# CW308T_M2351_Main.net
KiCad netlist of a schematic drawn in Altium Designer
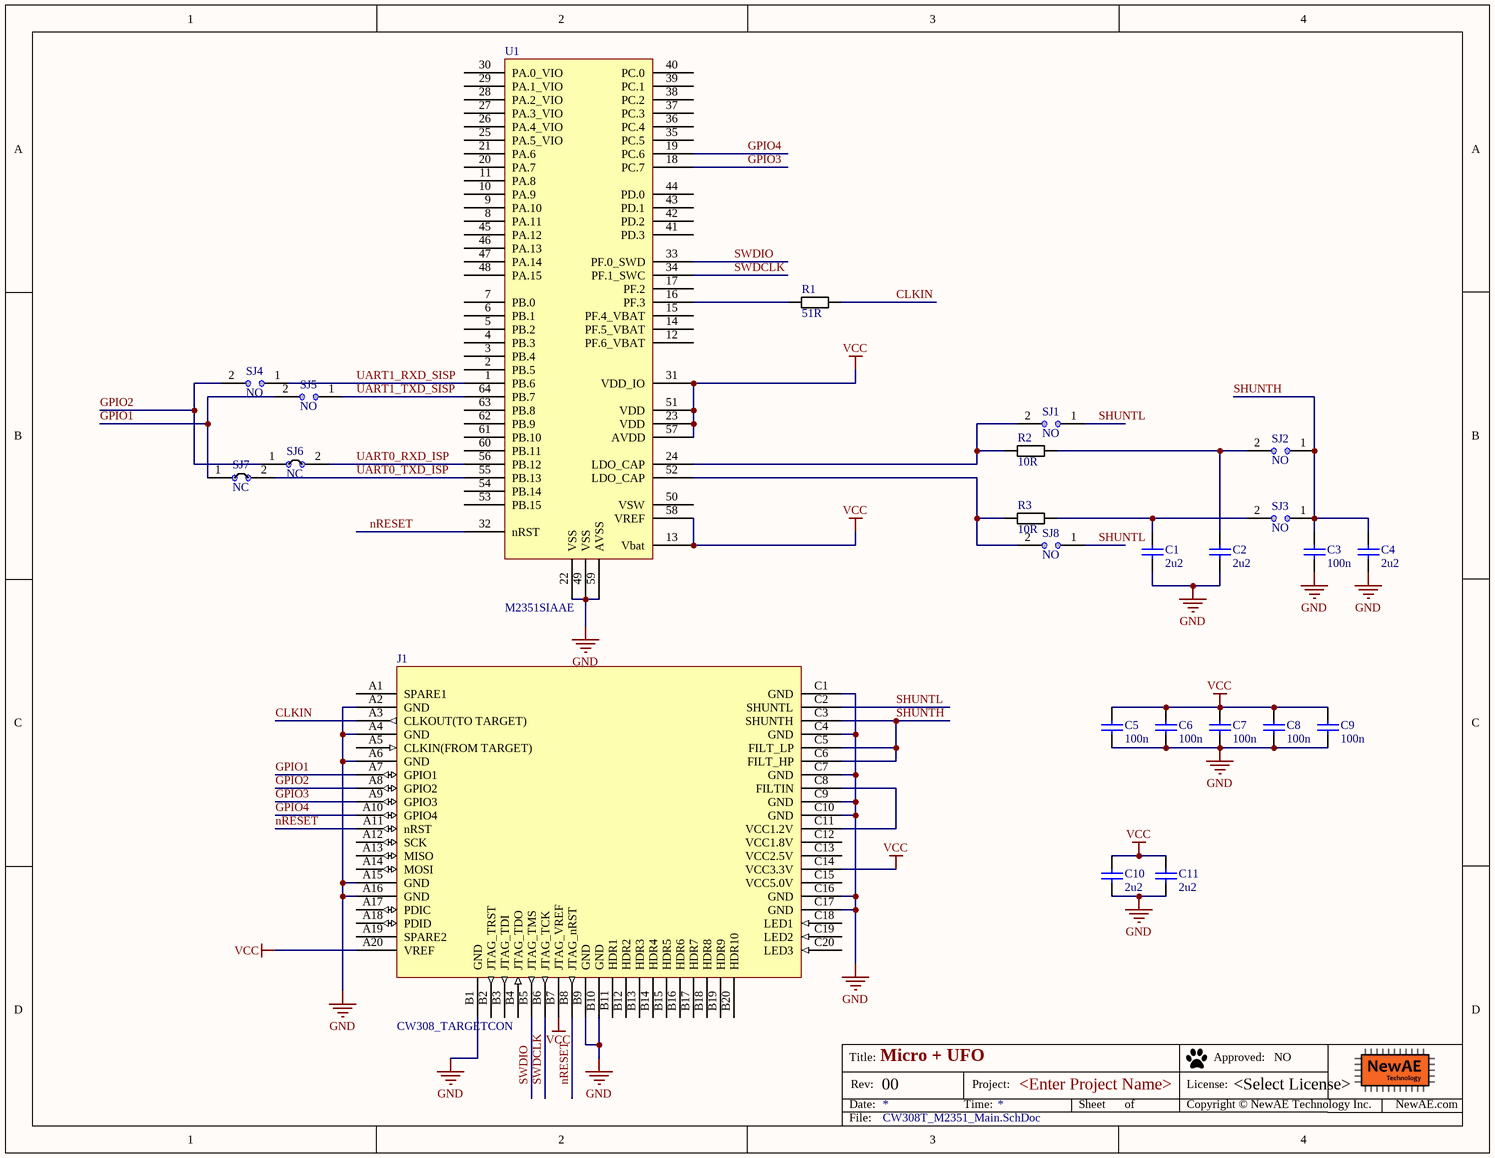
[diagram p0: CW308T_M2351_Main.SchDoc]

(export (version "E")
  (design (tool "Eeschema 10.0.6"))
  (components
    (comp (ref "C1")
      (value "2u2")
      (footprint "CAPC0603_M")
      (description "2u2, 0603")
      (fields (field (name "PART NUMBER") "CCHIP-2u2-0603"))
      (libsource (lib "NewAE_AltiumLib") (part "CAP"))
    )
    (comp (ref "C2")
      (value "2u2")
      (footprint "CAPC0603_M")
      (description "2u2, 0603")
      (fields (field (name "PART NUMBER") "CCHIP-2u2-0603"))
      (libsource (lib "NewAE_AltiumLib") (part "CAP"))
    )
    (comp (ref "C3")
      (value "100n")
      (footprint "CAPC0603_M")
      (description "100n, 0603")
      (fields (field (name "PART NUMBER") "CCHIP-100n-0603"))
      (libsource (lib "NewAE_AltiumLib") (part "CAP"))
    )
    (comp (ref "C4")
      (value "2u2")
      (footprint "CAPC0603_M")
      (description "2u2, 0603")
      (fields (field (name "PART NUMBER") "CCHIP-2u2-0603"))
      (libsource (lib "NewAE_AltiumLib") (part "CAP"))
    )
    (comp (ref "C5")
      (value "100n")
      (footprint "CAPC0603_M")
      (description "100n, 0603")
      (fields (field (name "PART NUMBER") "CCHIP-100n-0603"))
      (libsource (lib "NewAE_AltiumLib") (part "CAP"))
    )
    (comp (ref "C6")
      (value "100n")
      (footprint "CAPC0603_M")
      (description "100n, 0603")
      (fields (field (name "PART NUMBER") "CCHIP-100n-0603"))
      (libsource (lib "NewAE_AltiumLib") (part "CAP"))
    )
    (comp (ref "C7")
      (value "100n")
      (footprint "CAPC0603_M")
      (description "100n, 0603")
      (fields (field (name "PART NUMBER") "CCHIP-100n-0603"))
      (libsource (lib "NewAE_AltiumLib") (part "CAP"))
    )
    (comp (ref "C8")
      (value "100n")
      (footprint "CAPC0603_M")
      (description "100n, 0603")
      (fields (field (name "PART NUMBER") "CCHIP-100n-0603"))
      (libsource (lib "NewAE_AltiumLib") (part "CAP"))
    )
    (comp (ref "C9")
      (value "100n")
      (footprint "CAPC0603_M")
      (description "100n, 0603")
      (fields (field (name "PART NUMBER") "CCHIP-100n-0603"))
      (libsource (lib "NewAE_AltiumLib") (part "CAP"))
    )
    (comp (ref "C10")
      (value "2u2")
      (footprint "CAPC0603_M")
      (description "2u2, 0603")
      (fields (field (name "PART NUMBER") "CCHIP-2u2-0603"))
      (libsource (lib "NewAE_AltiumLib") (part "CAP"))
    )
    (comp (ref "C11")
      (value "2u2")
      (footprint "CAPC0603_M")
      (description "2u2, 0603")
      (fields (field (name "PART NUMBER") "CCHIP-2u2-0603"))
      (libsource (lib "NewAE_AltiumLib") (part "CAP"))
    )
    (comp (ref "J1")
      (value "CW308_TARGETCON")
      (footprint "CW308_TBOARD_CONN")
      (description "CW308 \"Standard\" Target Board Connector")
      (fields (field (name "PART NUMBER") "CW308_TBOARD"))
      (libsource (lib "NewAE_AltiumLib") (part "CW308_TBOARD"))
    )
    (comp (ref "R1")
      (value "51R")
      (footprint "RESC1608X55N")
      (description "51R res, 0603, 1%, 1/10W")
      (fields (field (name "PART NUMBER") "RCHIP-51R-0603") (field (name "TOLERANCE") "1%"))
      (libsource (lib "NewAE_AltiumLib") (part "RES-EU"))
    )
    (comp (ref "R2")
      (value "10R")
      (footprint "RESC1608X55N")
      (description "10R res, 0603, 1%, 1/10W")
      (fields (field (name "PART NUMBER") "RCHIP-10R-0603") (field (name "TOLERANCE") "1%"))
      (libsource (lib "NewAE_AltiumLib") (part "RES-EU"))
    )
    (comp (ref "R3")
      (value "10R")
      (footprint "RESC1608X55N")
      (description "10R res, 0603, 1%, 1/10W")
      (fields (field (name "PART NUMBER") "RCHIP-10R-0603") (field (name "TOLERANCE") "1%"))
      (libsource (lib "NewAE_AltiumLib") (part "RES-EU"))
    )
    (comp (ref "SJ1")
      (value "NO")
      (footprint "SJ_2S_NO")
      (description "Solder Jumper, NO")
      (fields (field (name "PART NUMBER") "SJ_2S_NO"))
      (libsource (lib "NewAE_AltiumLib") (part "SJ_2S_NO"))
    )
    (comp (ref "SJ2")
      (value "NO")
      (footprint "SJ_2S_NO")
      (description "Solder Jumper, NO")
      (fields (field (name "PART NUMBER") "SJ_2S_NO"))
      (libsource (lib "NewAE_AltiumLib") (part "SJ_2S_NO"))
    )
    (comp (ref "SJ3")
      (value "NO")
      (footprint "SJ_2S_NO")
      (description "Solder Jumper, NO")
      (fields (field (name "PART NUMBER") "SJ_2S_NO"))
      (libsource (lib "NewAE_AltiumLib") (part "SJ_2S_NO"))
    )
    (comp (ref "SJ4")
      (value "NO")
      (footprint "SJ_2S_NO")
      (description "Solder Jumper, NO")
      (fields (field (name "PART NUMBER") "SJ_2S_NO"))
      (libsource (lib "NewAE_AltiumLib") (part "SJ_2S_NO"))
    )
    (comp (ref "SJ5")
      (value "NO")
      (footprint "SJ_2S_NO")
      (description "Solder Jumper, NO")
      (fields (field (name "PART NUMBER") "SJ_2S_NO"))
      (libsource (lib "NewAE_AltiumLib") (part "SJ_2S_NO"))
    )
    (comp (ref "SJ6")
      (value "NC")
      (footprint "SJ_2S_NC")
      (description "Solder Jumper, NC")
      (fields (field (name "PART NUMBER") "SJ_2S"))
      (libsource (lib "NewAE_AltiumLib") (part "SJ_2S"))
    )
    (comp (ref "SJ7")
      (value "NC")
      (footprint "SJ_2S_NC")
      (description "Solder Jumper, NC")
      (fields (field (name "PART NUMBER") "SJ_2S"))
      (libsource (lib "NewAE_AltiumLib") (part "SJ_2S"))
    )
    (comp (ref "SJ8")
      (value "NO")
      (footprint "SJ_2S_NO")
      (description "Solder Jumper, NO")
      (fields (field (name "PART NUMBER") "SJ_2S_NO"))
      (libsource (lib "NewAE_AltiumLib") (part "SJ_2S_NO"))
    )
    (comp (ref "U1")
      (value "M2351SIAAE")
      (footprint "TQFP50P1200X1200X120-64N")
      (description "Cortex M23 Device, QFP64")
      (libsource (lib "NewAE_AltiumLib") (part "M2351SIAAE"))
    )
  )
  (nets
    (net (code "1") (name "/CLKIN") (class "Default")
      (node (ref "J1") (pin "A3") (pinfunction "CLKOUT(TO_TARGET)_A3") (pintype "output"))
      (node (ref "R1") (pin "2") (pinfunction "2_2") (pintype "passive"))
    )
    (net (code "2") (name "/GPIO1") (class "Default")
      (node (ref "J1") (pin "A7") (pinfunction "GPIO1_A7") (pintype "bidirectional"))
      (node (ref "SJ5") (pin "2") (pinfunction "2_2") (pintype "passive"))
      (node (ref "SJ7") (pin "1") (pinfunction "1_1") (pintype "passive"))
    )
    (net (code "3") (name "/GPIO2") (class "Default")
      (node (ref "J1") (pin "A8") (pinfunction "GPIO2_A8") (pintype "bidirectional"))
      (node (ref "SJ4") (pin "2") (pinfunction "2_2") (pintype "passive"))
      (node (ref "SJ6") (pin "1") (pinfunction "1_1") (pintype "passive"))
    )
    (net (code "4") (name "/GPIO3") (class "Default")
      (node (ref "J1") (pin "A9") (pinfunction "GPIO3_A9") (pintype "bidirectional"))
      (node (ref "U1") (pin "18") (pinfunction "PC.7_18") (pintype "passive"))
    )
    (net (code "5") (name "/GPIO4") (class "Default")
      (node (ref "J1") (pin "A10") (pinfunction "GPIO4_A10") (pintype "bidirectional"))
      (node (ref "U1") (pin "19") (pinfunction "PC.6_19") (pintype "passive"))
    )
    (net (code "6") (name "/SHUNTH") (class "Default")
      (node (ref "C3") (pin "1") (pinfunction "1_1") (pintype "passive"))
      (node (ref "C4") (pin "1") (pinfunction "1_1") (pintype "passive"))
      (node (ref "J1") (pin "C3") (pinfunction "SHUNTH_C3") (pintype "passive"))
      (node (ref "J1") (pin "C5") (pinfunction "FILT_LP_C5") (pintype "passive"))
      (node (ref "J1") (pin "C6") (pinfunction "FILT_HP_C6") (pintype "passive"))
      (node (ref "SJ2") (pin "1") (pinfunction "1_1") (pintype "passive"))
      (node (ref "SJ3") (pin "1") (pinfunction "1_1") (pintype "passive"))
    )
    (net (code "7") (name "/SHUNTL") (class "Default")
      (node (ref "J1") (pin "C2") (pinfunction "SHUNTL_C2") (pintype "passive"))
      (node (ref "SJ1") (pin "1") (pinfunction "1_1") (pintype "passive"))
      (node (ref "SJ8") (pin "1") (pinfunction "1_1") (pintype "passive"))
    )
    (net (code "8") (name "/SWDCLK") (class "Default")
      (node (ref "J1") (pin "B6") (pinfunction "JTAG_TCK_B6") (pintype "output"))
      (node (ref "U1") (pin "34") (pinfunction "PF.1_SWC_34") (pintype "passive"))
    )
    (net (code "9") (name "/SWDIO") (class "Default")
      (node (ref "J1") (pin "B5") (pinfunction "JTAG_TMS_B5") (pintype "output"))
      (node (ref "U1") (pin "33") (pinfunction "PF.0_SWD_33") (pintype "passive"))
    )
    (net (code "10") (name "/UART0_RXD_ISP") (class "Default")
      (node (ref "SJ6") (pin "2") (pinfunction "2_2") (pintype "passive"))
      (node (ref "U1") (pin "56") (pinfunction "PB.12_56") (pintype "passive"))
    )
    (net (code "11") (name "/UART0_TXD_ISP") (class "Default")
      (node (ref "SJ7") (pin "2") (pinfunction "2_2") (pintype "passive"))
      (node (ref "U1") (pin "55") (pinfunction "PB.13_55") (pintype "passive"))
    )
    (net (code "12") (name "/UART1_RXD_SISP") (class "Default")
      (node (ref "SJ4") (pin "1") (pinfunction "1_1") (pintype "passive"))
      (node (ref "U1") (pin "1") (pinfunction "PB.6_1") (pintype "passive"))
    )
    (net (code "13") (name "/UART1_TXD_SISP") (class "Default")
      (node (ref "SJ5") (pin "1") (pinfunction "1_1") (pintype "passive"))
      (node (ref "U1") (pin "64") (pinfunction "PB.7_64") (pintype "passive"))
    )
    (net (code "14") (name "/nRESET") (class "Default")
      (node (ref "J1") (pin "A11") (pinfunction "nRST_A11") (pintype "bidirectional"))
      (node (ref "J1") (pin "B8") (pinfunction "JTAG_nRST_B8") (pintype "output"))
      (node (ref "U1") (pin "32") (pinfunction "nRST_32") (pintype "passive"))
    )
    (net (code "15") (name "GND") (class "Default")
      (node (ref "C1") (pin "2") (pinfunction "2_2") (pintype "passive"))
      (node (ref "C10") (pin "2") (pinfunction "2_2") (pintype "passive"))
      (node (ref "C11") (pin "2") (pinfunction "2_2") (pintype "passive"))
      (node (ref "C2") (pin "2") (pinfunction "2_2") (pintype "passive"))
      (node (ref "C3") (pin "2") (pinfunction "2_2") (pintype "passive"))
      (node (ref "C4") (pin "2") (pinfunction "2_2") (pintype "passive"))
      (node (ref "C5") (pin "2") (pinfunction "2_2") (pintype "passive"))
      (node (ref "C6") (pin "2") (pinfunction "2_2") (pintype "passive"))
      (node (ref "C7") (pin "2") (pinfunction "2_2") (pintype "passive"))
      (node (ref "C8") (pin "2") (pinfunction "2_2") (pintype "passive"))
      (node (ref "C9") (pin "2") (pinfunction "2_2") (pintype "passive"))
      (node (ref "J1") (pin "A15") (pinfunction "GND_A15") (pintype "passive"))
      (node (ref "J1") (pin "A16") (pinfunction "GND_A16") (pintype "passive"))
      (node (ref "J1") (pin "A2") (pinfunction "GND_A2") (pintype "passive"))
      (node (ref "J1") (pin "A4") (pinfunction "GND_A4") (pintype "passive"))
      (node (ref "J1") (pin "A6") (pinfunction "GND_A6") (pintype "power_in"))
      (node (ref "J1") (pin "B1") (pinfunction "GND_B1") (pintype "passive"))
      (node (ref "J1") (pin "B10") (pinfunction "GND_B10") (pintype "passive"))
      (node (ref "J1") (pin "B9") (pinfunction "GND_B9") (pintype "passive"))
      (node (ref "J1") (pin "C1") (pinfunction "GND_C1") (pintype "power_in"))
      (node (ref "J1") (pin "C10") (pinfunction "GND_C10") (pintype "power_in"))
      (node (ref "J1") (pin "C16") (pinfunction "GND_C16") (pintype "power_in"))
      (node (ref "J1") (pin "C17") (pinfunction "GND_C17") (pintype "power_in"))
      (node (ref "J1") (pin "C4") (pinfunction "GND_C4") (pintype "power_in"))
      (node (ref "J1") (pin "C7") (pinfunction "GND_C7") (pintype "power_in"))
      (node (ref "J1") (pin "C9") (pinfunction "GND_C9") (pintype "power_in"))
      (node (ref "U1") (pin "22") (pinfunction "VSS_22") (pintype "passive"))
      (node (ref "U1") (pin "49") (pinfunction "VSS_49") (pintype "passive"))
      (node (ref "U1") (pin "59") (pinfunction "AVSS_59") (pintype "passive"))
    )
    (net (code "16") (name "Net-(C1-Pad1)") (class "Default")
      (node (ref "C1") (pin "1") (pinfunction "1_1") (pintype "passive"))
      (node (ref "R3") (pin "2") (pinfunction "2_2") (pintype "passive"))
      (node (ref "SJ3") (pin "2") (pinfunction "2_2") (pintype "passive"))
    )
    (net (code "17") (name "Net-(C2-Pad1)") (class "Default")
      (node (ref "C2") (pin "1") (pinfunction "1_1") (pintype "passive"))
      (node (ref "R2") (pin "2") (pinfunction "2_2") (pintype "passive"))
      (node (ref "SJ2") (pin "2") (pinfunction "2_2") (pintype "passive"))
    )
    (net (code "18") (name "Net-(J1-FILTIN)") (class "Default")
      (node (ref "J1") (pin "C11") (pinfunction "VCC1.2V_C11") (pintype "power_in"))
      (node (ref "J1") (pin "C8") (pinfunction "FILTIN_C8") (pintype "passive"))
    )
    (net (code "19") (name "Net-(R2-Pad1)") (class "Default")
      (node (ref "R2") (pin "1") (pinfunction "1_1") (pintype "passive"))
      (node (ref "SJ1") (pin "2") (pinfunction "2_2") (pintype "passive"))
      (node (ref "U1") (pin "24") (pinfunction "LDO_CAP_24") (pintype "passive"))
    )
    (net (code "20") (name "Net-(R3-Pad1)") (class "Default")
      (node (ref "R3") (pin "1") (pinfunction "1_1") (pintype "passive"))
      (node (ref "SJ8") (pin "2") (pinfunction "2_2") (pintype "passive"))
      (node (ref "U1") (pin "52") (pinfunction "LDO_CAP_52") (pintype "passive"))
    )
    (net (code "21") (name "Net-(U1-PF.3)") (class "Default")
      (node (ref "R1") (pin "1") (pinfunction "1_1") (pintype "passive"))
      (node (ref "U1") (pin "16") (pinfunction "PF.3_16") (pintype "passive"))
    )
    (net (code "22") (name "VCC") (class "Default")
      (node (ref "C10") (pin "1") (pinfunction "1_1") (pintype "passive"))
      (node (ref "C11") (pin "1") (pinfunction "1_1") (pintype "passive"))
      (node (ref "C5") (pin "1") (pinfunction "1_1") (pintype "passive"))
      (node (ref "C6") (pin "1") (pinfunction "1_1") (pintype "passive"))
      (node (ref "C7") (pin "1") (pinfunction "1_1") (pintype "passive"))
      (node (ref "C8") (pin "1") (pinfunction "1_1") (pintype "passive"))
      (node (ref "C9") (pin "1") (pinfunction "1_1") (pintype "passive"))
      (node (ref "J1") (pin "A20") (pinfunction "VREF_A20") (pintype "tri_state"))
      (node (ref "J1") (pin "B7") (pinfunction "JTAG_VREF_B7") (pintype "tri_state"))
      (node (ref "J1") (pin "C14") (pinfunction "VCC3.3V_C14") (pintype "power_in"))
      (node (ref "U1") (pin "13") (pinfunction "Vbat_13") (pintype "passive"))
      (node (ref "U1") (pin "23") (pinfunction "VDD_23") (pintype "passive"))
      (node (ref "U1") (pin "31") (pinfunction "VDD_IO_31") (pintype "passive"))
      (node (ref "U1") (pin "51") (pinfunction "VDD_51") (pintype "passive"))
      (node (ref "U1") (pin "57") (pinfunction "AVDD_57") (pintype "passive"))
      (node (ref "U1") (pin "58") (pinfunction "VREF_58") (pintype "passive"))
    )
    (net (code "23") (name "unconnected-(J1-CLKIN(FROM_TARGET)-PadA5)") (class "Default")
      (node (ref "J1") (pin "A5") (pinfunction "CLKIN(FROM_TARGET)_A5") (pintype "input"))
    )
    (net (code "24") (name "unconnected-(J1-HDR1-PadB11)") (class "Default")
      (node (ref "J1") (pin "B11") (pinfunction "HDR1_B11") (pintype "passive"))
    )
    (net (code "25") (name "unconnected-(J1-HDR2-PadB12)") (class "Default")
      (node (ref "J1") (pin "B12") (pinfunction "HDR2_B12") (pintype "passive"))
    )
    (net (code "26") (name "unconnected-(J1-HDR3-PadB13)") (class "Default")
      (node (ref "J1") (pin "B13") (pinfunction "HDR3_B13") (pintype "passive"))
    )
    (net (code "27") (name "unconnected-(J1-HDR4-PadB14)") (class "Default")
      (node (ref "J1") (pin "B14") (pinfunction "HDR4_B14") (pintype "passive"))
    )
    (net (code "28") (name "unconnected-(J1-HDR5-PadB15)") (class "Default")
      (node (ref "J1") (pin "B15") (pinfunction "HDR5_B15") (pintype "passive"))
    )
    (net (code "29") (name "unconnected-(J1-HDR6-PadB16)") (class "Default")
      (node (ref "J1") (pin "B16") (pinfunction "HDR6_B16") (pintype "passive"))
    )
    (net (code "30") (name "unconnected-(J1-HDR7-PadB17)") (class "Default")
      (node (ref "J1") (pin "B17") (pinfunction "HDR7_B17") (pintype "passive"))
    )
    (net (code "31") (name "unconnected-(J1-HDR8-PadB18)") (class "Default")
      (node (ref "J1") (pin "B18") (pinfunction "HDR8_B18") (pintype "passive"))
    )
    (net (code "32") (name "unconnected-(J1-HDR9-PadB19)") (class "Default")
      (node (ref "J1") (pin "B19") (pinfunction "HDR9_B19") (pintype "passive"))
    )
    (net (code "33") (name "unconnected-(J1-HDR10-PadB20)") (class "Default")
      (node (ref "J1") (pin "B20") (pinfunction "HDR10_B20") (pintype "passive"))
    )
    (net (code "34") (name "unconnected-(J1-JTAG_TDI-PadB3)") (class "Default")
      (node (ref "J1") (pin "B3") (pinfunction "JTAG_TDI_B3") (pintype "output"))
    )
    (net (code "35") (name "unconnected-(J1-JTAG_TDO-PadB4)") (class "Default")
      (node (ref "J1") (pin "B4") (pinfunction "JTAG_TDO_B4") (pintype "input"))
    )
    (net (code "36") (name "unconnected-(J1-JTAG_TRST-PadB2)") (class "Default")
      (node (ref "J1") (pin "B2") (pinfunction "JTAG_TRST_B2") (pintype "output"))
    )
    (net (code "37") (name "unconnected-(J1-LED1-PadC18)") (class "Default")
      (node (ref "J1") (pin "C18") (pinfunction "LED1_C18") (pintype "input"))
    )
    (net (code "38") (name "unconnected-(J1-LED2-PadC19)") (class "Default")
      (node (ref "J1") (pin "C19") (pinfunction "LED2_C19") (pintype "input"))
    )
    (net (code "39") (name "unconnected-(J1-LED3-PadC20)") (class "Default")
      (node (ref "J1") (pin "C20") (pinfunction "LED3_C20") (pintype "input"))
    )
    (net (code "40") (name "unconnected-(J1-MISO-PadA13)") (class "Default")
      (node (ref "J1") (pin "A13") (pinfunction "MISO_A13") (pintype "bidirectional"))
    )
    (net (code "41") (name "unconnected-(J1-MOSI-PadA14)") (class "Default")
      (node (ref "J1") (pin "A14") (pinfunction "MOSI_A14") (pintype "bidirectional"))
    )
    (net (code "42") (name "unconnected-(J1-PDIC-PadA17)") (class "Default")
      (node (ref "J1") (pin "A17") (pinfunction "PDIC_A17") (pintype "bidirectional"))
    )
    (net (code "43") (name "unconnected-(J1-PDID-PadA18)") (class "Default")
      (node (ref "J1") (pin "A18") (pinfunction "PDID_A18") (pintype "bidirectional"))
    )
    (net (code "44") (name "unconnected-(J1-SCK-PadA12)") (class "Default")
      (node (ref "J1") (pin "A12") (pinfunction "SCK_A12") (pintype "bidirectional"))
    )
    (net (code "45") (name "unconnected-(J1-SPARE1-PadA1)") (class "Default")
      (node (ref "J1") (pin "A1") (pinfunction "SPARE1_A1") (pintype "passive"))
    )
    (net (code "46") (name "unconnected-(J1-SPARE2-PadA19)") (class "Default")
      (node (ref "J1") (pin "A19") (pinfunction "SPARE2_A19") (pintype "passive"))
    )
    (net (code "47") (name "unconnected-(J1-VCC1.8V-PadC12)") (class "Default")
      (node (ref "J1") (pin "C12") (pinfunction "VCC1.8V_C12") (pintype "power_in"))
    )
    (net (code "48") (name "unconnected-(J1-VCC2.5V-PadC13)") (class "Default")
      (node (ref "J1") (pin "C13") (pinfunction "VCC2.5V_C13") (pintype "power_in"))
    )
    (net (code "49") (name "unconnected-(J1-VCC5.0V-PadC15)") (class "Default")
      (node (ref "J1") (pin "C15") (pinfunction "VCC5.0V_C15") (pintype "power_in"))
    )
    (net (code "50") (name "unconnected-(U1-PA.0_VIO-Pad30)") (class "Default")
      (node (ref "U1") (pin "30") (pinfunction "PA.0_VIO_30") (pintype "passive"))
    )
    (net (code "51") (name "unconnected-(U1-PA.1_VIO-Pad29)") (class "Default")
      (node (ref "U1") (pin "29") (pinfunction "PA.1_VIO_29") (pintype "passive"))
    )
    (net (code "52") (name "unconnected-(U1-PA.2_VIO-Pad28)") (class "Default")
      (node (ref "U1") (pin "28") (pinfunction "PA.2_VIO_28") (pintype "passive"))
    )
    (net (code "53") (name "unconnected-(U1-PA.3_VIO-Pad27)") (class "Default")
      (node (ref "U1") (pin "27") (pinfunction "PA.3_VIO_27") (pintype "passive"))
    )
    (net (code "54") (name "unconnected-(U1-PA.4_VIO-Pad26)") (class "Default")
      (node (ref "U1") (pin "26") (pinfunction "PA.4_VIO_26") (pintype "passive"))
    )
    (net (code "55") (name "unconnected-(U1-PA.5_VIO-Pad25)") (class "Default")
      (node (ref "U1") (pin "25") (pinfunction "PA.5_VIO_25") (pintype "passive"))
    )
    (net (code "56") (name "unconnected-(U1-PA.6-Pad21)") (class "Default")
      (node (ref "U1") (pin "21") (pinfunction "PA.6_21") (pintype "passive"))
    )
    (net (code "57") (name "unconnected-(U1-PA.7-Pad20)") (class "Default")
      (node (ref "U1") (pin "20") (pinfunction "PA.7_20") (pintype "passive"))
    )
    (net (code "58") (name "unconnected-(U1-PA.8-Pad11)") (class "Default")
      (node (ref "U1") (pin "11") (pinfunction "PA.8_11") (pintype "passive"))
    )
    (net (code "59") (name "unconnected-(U1-PA.9-Pad10)") (class "Default")
      (node (ref "U1") (pin "10") (pinfunction "PA.9_10") (pintype "passive"))
    )
    (net (code "60") (name "unconnected-(U1-PA.10-Pad9)") (class "Default")
      (node (ref "U1") (pin "9") (pinfunction "PA.10_9") (pintype "passive"))
    )
    (net (code "61") (name "unconnected-(U1-PA.11-Pad8)") (class "Default")
      (node (ref "U1") (pin "8") (pinfunction "PA.11_8") (pintype "passive"))
    )
    (net (code "62") (name "unconnected-(U1-PA.12-Pad45)") (class "Default")
      (node (ref "U1") (pin "45") (pinfunction "PA.12_45") (pintype "passive"))
    )
    (net (code "63") (name "unconnected-(U1-PA.13-Pad46)") (class "Default")
      (node (ref "U1") (pin "46") (pinfunction "PA.13_46") (pintype "passive"))
    )
    (net (code "64") (name "unconnected-(U1-PA.14-Pad47)") (class "Default")
      (node (ref "U1") (pin "47") (pinfunction "PA.14_47") (pintype "passive"))
    )
    (net (code "65") (name "unconnected-(U1-PA.15-Pad48)") (class "Default")
      (node (ref "U1") (pin "48") (pinfunction "PA.15_48") (pintype "passive"))
    )
    (net (code "66") (name "unconnected-(U1-PB.0-Pad7)") (class "Default")
      (node (ref "U1") (pin "7") (pinfunction "PB.0_7") (pintype "passive"))
    )
    (net (code "67") (name "unconnected-(U1-PB.1-Pad6)") (class "Default")
      (node (ref "U1") (pin "6") (pinfunction "PB.1_6") (pintype "passive"))
    )
    (net (code "68") (name "unconnected-(U1-PB.2-Pad5)") (class "Default")
      (node (ref "U1") (pin "5") (pinfunction "PB.2_5") (pintype "passive"))
    )
    (net (code "69") (name "unconnected-(U1-PB.3-Pad4)") (class "Default")
      (node (ref "U1") (pin "4") (pinfunction "PB.3_4") (pintype "passive"))
    )
    (net (code "70") (name "unconnected-(U1-PB.4-Pad3)") (class "Default")
      (node (ref "U1") (pin "3") (pinfunction "PB.4_3") (pintype "passive"))
    )
    (net (code "71") (name "unconnected-(U1-PB.5-Pad2)") (class "Default")
      (node (ref "U1") (pin "2") (pinfunction "PB.5_2") (pintype "passive"))
    )
    (net (code "72") (name "unconnected-(U1-PB.8-Pad63)") (class "Default")
      (node (ref "U1") (pin "63") (pinfunction "PB.8_63") (pintype "passive"))
    )
    (net (code "73") (name "unconnected-(U1-PB.9-Pad62)") (class "Default")
      (node (ref "U1") (pin "62") (pinfunction "PB.9_62") (pintype "passive"))
    )
    (net (code "74") (name "unconnected-(U1-PB.10-Pad61)") (class "Default")
      (node (ref "U1") (pin "61") (pinfunction "PB.10_61") (pintype "passive"))
    )
    (net (code "75") (name "unconnected-(U1-PB.11-Pad60)") (class "Default")
      (node (ref "U1") (pin "60") (pinfunction "PB.11_60") (pintype "passive"))
    )
    (net (code "76") (name "unconnected-(U1-PB.14-Pad54)") (class "Default")
      (node (ref "U1") (pin "54") (pinfunction "PB.14_54") (pintype "passive"))
    )
    (net (code "77") (name "unconnected-(U1-PB.15-Pad53)") (class "Default")
      (node (ref "U1") (pin "53") (pinfunction "PB.15_53") (pintype "passive"))
    )
    (net (code "78") (name "unconnected-(U1-PC.0-Pad40)") (class "Default")
      (node (ref "U1") (pin "40") (pinfunction "PC.0_40") (pintype "passive"))
    )
    (net (code "79") (name "unconnected-(U1-PC.1-Pad39)") (class "Default")
      (node (ref "U1") (pin "39") (pinfunction "PC.1_39") (pintype "passive"))
    )
    (net (code "80") (name "unconnected-(U1-PC.2-Pad38)") (class "Default")
      (node (ref "U1") (pin "38") (pinfunction "PC.2_38") (pintype "passive"))
    )
    (net (code "81") (name "unconnected-(U1-PC.3-Pad37)") (class "Default")
      (node (ref "U1") (pin "37") (pinfunction "PC.3_37") (pintype "passive"))
    )
    (net (code "82") (name "unconnected-(U1-PC.4-Pad36)") (class "Default")
      (node (ref "U1") (pin "36") (pinfunction "PC.4_36") (pintype "passive"))
    )
    (net (code "83") (name "unconnected-(U1-PC.5-Pad35)") (class "Default")
      (node (ref "U1") (pin "35") (pinfunction "PC.5_35") (pintype "passive"))
    )
    (net (code "84") (name "unconnected-(U1-PD.0-Pad44)") (class "Default")
      (node (ref "U1") (pin "44") (pinfunction "PD.0_44") (pintype "passive"))
    )
    (net (code "85") (name "unconnected-(U1-PD.1-Pad43)") (class "Default")
      (node (ref "U1") (pin "43") (pinfunction "PD.1_43") (pintype "passive"))
    )
    (net (code "86") (name "unconnected-(U1-PD.2-Pad42)") (class "Default")
      (node (ref "U1") (pin "42") (pinfunction "PD.2_42") (pintype "passive"))
    )
    (net (code "87") (name "unconnected-(U1-PD.3-Pad41)") (class "Default")
      (node (ref "U1") (pin "41") (pinfunction "PD.3_41") (pintype "passive"))
    )
    (net (code "88") (name "unconnected-(U1-PF.2-Pad17)") (class "Default")
      (node (ref "U1") (pin "17") (pinfunction "PF.2_17") (pintype "passive"))
    )
    (net (code "89") (name "unconnected-(U1-PF.4_VBAT-Pad15)") (class "Default")
      (node (ref "U1") (pin "15") (pinfunction "PF.4_VBAT_15") (pintype "passive"))
    )
    (net (code "90") (name "unconnected-(U1-PF.5_VBAT-Pad14)") (class "Default")
      (node (ref "U1") (pin "14") (pinfunction "PF.5_VBAT_14") (pintype "passive"))
    )
    (net (code "91") (name "unconnected-(U1-PF.6_VBAT-Pad12)") (class "Default")
      (node (ref "U1") (pin "12") (pinfunction "PF.6_VBAT_12") (pintype "passive"))
    )
    (net (code "92") (name "unconnected-(U1-VSW-Pad50)") (class "Default")
      (node (ref "U1") (pin "50") (pinfunction "VSW_50") (pintype "passive"))
    )
  )
)
